# Over_Discharge_Protection_SCHEMATIC.net
KiCad netlist of a schematic drawn in Altium Designer
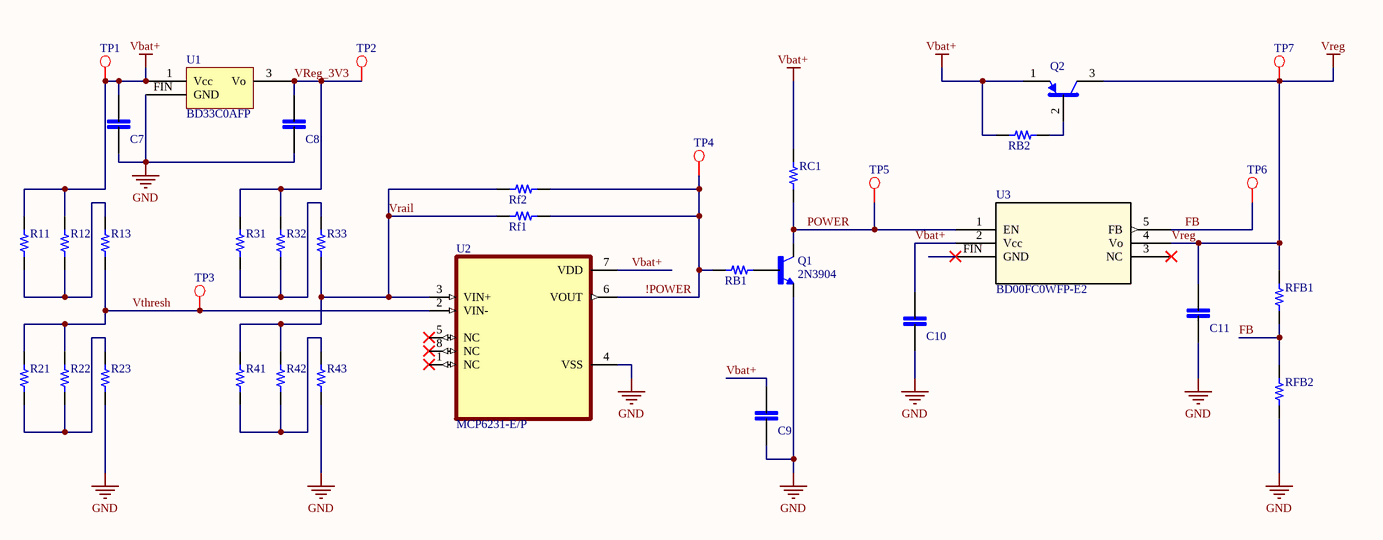
[diagram p0: Over Discharge Protection_SCHEMATIC.SchDoc]

(export (version "E")
  (design (tool "Eeschema 10.0.6"))
  (components
    (comp (ref "C7")
      (value "0805")
      (footprint "Capacitor 0805")
      (libsource (lib "GamePi SCH LIB") (part "Capacitor 0805"))
    )
    (comp (ref "C8")
      (value "0805")
      (footprint "Capacitor 0805")
      (libsource (lib "GamePi SCH LIB") (part "Capacitor 0805"))
    )
    (comp (ref "C9")
      (value "0805")
      (footprint "Capacitor 0805")
      (libsource (lib "GamePi SCH LIB") (part "Capacitor 0805"))
    )
    (comp (ref "C10")
      (value "0805")
      (footprint "Capacitor 0805")
      (libsource (lib "GamePi SCH LIB") (part "Capacitor 0805"))
    )
    (comp (ref "C11")
      (value "0805")
      (footprint "Capacitor 0805")
      (libsource (lib "GamePi SCH LIB") (part "Capacitor 0805"))
    )
    (comp (ref "Q1") (value "2N3904") (footprint "2N3904") (libsource (lib "GamePi SCH LIB") (part "2N3904")))
    (comp (ref "Q2") (value "2N3906") (footprint "2N3904") (libsource (lib "GamePi SCH LIB") (part "2N3906")))
    (comp (ref "R11")
      (value "Resistor Axial")
      (footprint "Resistor Axial")
      (libsource (lib "GamePi SCH LIB") (part "Resistor Axial"))
    )
    (comp (ref "R12")
      (value "Resistor Axial")
      (footprint "Resistor Axial")
      (libsource (lib "GamePi SCH LIB") (part "Resistor Axial"))
    )
    (comp (ref "R13")
      (value "Resistor Axial")
      (footprint "Resistor Axial")
      (libsource (lib "GamePi SCH LIB") (part "Resistor Axial"))
    )
    (comp (ref "R21")
      (value "Resistor Axial")
      (footprint "Resistor Axial")
      (libsource (lib "GamePi SCH LIB") (part "Resistor Axial"))
    )
    (comp (ref "R22")
      (value "Resistor Axial")
      (footprint "Resistor Axial")
      (libsource (lib "GamePi SCH LIB") (part "Resistor Axial"))
    )
    (comp (ref "R23")
      (value "Resistor Axial")
      (footprint "Resistor Axial")
      (libsource (lib "GamePi SCH LIB") (part "Resistor Axial"))
    )
    (comp (ref "R31")
      (value "Resistor Axial")
      (footprint "Resistor Axial")
      (libsource (lib "GamePi SCH LIB") (part "Resistor Axial"))
    )
    (comp (ref "R32")
      (value "Resistor Axial")
      (footprint "Resistor Axial")
      (libsource (lib "GamePi SCH LIB") (part "Resistor Axial"))
    )
    (comp (ref "R33")
      (value "Resistor Axial")
      (footprint "Resistor Axial")
      (libsource (lib "GamePi SCH LIB") (part "Resistor Axial"))
    )
    (comp (ref "R41")
      (value "Resistor Axial")
      (footprint "Resistor Axial")
      (libsource (lib "GamePi SCH LIB") (part "Resistor Axial"))
    )
    (comp (ref "R42")
      (value "Resistor Axial")
      (footprint "Resistor Axial")
      (libsource (lib "GamePi SCH LIB") (part "Resistor Axial"))
    )
    (comp (ref "R43")
      (value "Resistor Axial")
      (footprint "Resistor Axial")
      (libsource (lib "GamePi SCH LIB") (part "Resistor Axial"))
    )
    (comp (ref "RB1")
      (value "Resistor Axial")
      (footprint "Resistor Axial")
      (libsource (lib "GamePi SCH LIB") (part "Resistor Axial"))
    )
    (comp (ref "RB2")
      (value "Resistor Axial")
      (footprint "Resistor Axial")
      (libsource (lib "GamePi SCH LIB") (part "Resistor Axial"))
    )
    (comp (ref "RC1")
      (value "Resistor Axial")
      (footprint "Resistor Axial")
      (libsource (lib "GamePi SCH LIB") (part "Resistor Axial"))
    )
    (comp (ref "Rf1")
      (value "Resistor Axial")
      (footprint "Resistor Axial")
      (libsource (lib "GamePi SCH LIB") (part "Resistor Axial"))
    )
    (comp (ref "Rf2")
      (value "Resistor Axial")
      (footprint "Resistor Axial")
      (libsource (lib "GamePi SCH LIB") (part "Resistor Axial"))
    )
    (comp (ref "RFB1")
      (value "Resistor Axial")
      (footprint "Resistor Axial")
      (libsource (lib "GamePi SCH LIB") (part "Resistor Axial"))
    )
    (comp (ref "RFB2")
      (value "Resistor Axial")
      (footprint "Resistor Axial")
      (libsource (lib "GamePi SCH LIB") (part "Resistor Axial"))
    )
    (comp (ref "TP1")
      (value "Test Point")
      (footprint "Test Point")
      (libsource (lib "GamePi SCH LIB") (part "Test Point"))
    )
    (comp (ref "TP2")
      (value "Test Point")
      (footprint "Test Point")
      (libsource (lib "GamePi SCH LIB") (part "Test Point"))
    )
    (comp (ref "TP3")
      (value "Test Point")
      (footprint "Test Point")
      (libsource (lib "GamePi SCH LIB") (part "Test Point"))
    )
    (comp (ref "TP4")
      (value "Test Point")
      (footprint "Test Point")
      (libsource (lib "GamePi SCH LIB") (part "Test Point"))
    )
    (comp (ref "TP5")
      (value "Test Point")
      (footprint "Test Point")
      (libsource (lib "GamePi SCH LIB") (part "Test Point"))
    )
    (comp (ref "TP6")
      (value "Test Point")
      (footprint "Test Point")
      (libsource (lib "GamePi SCH LIB") (part "Test Point"))
    )
    (comp (ref "TP7")
      (value "Test Point")
      (footprint "Test Point")
      (libsource (lib "GamePi SCH LIB") (part "Test Point"))
    )
    (comp (ref "U1")
      (value "BD33C0AFP")
      (footprint "BD33C0AFP")
      (libsource (lib "GamePi SCH LIB") (part "BD33C0AFP"))
    )
    (comp (ref "U2")
      (value "MCP6231-E/P")
      (footprint "MCP6231-E/P")
      (libsource (lib "GamePi SCH LIB") (part "MCP6231-E/P"))
    )
    (comp (ref "U3")
      (value "BD00FC0WFP-E2")
      (footprint "BD00FC0WFP-E2")
      (libsource (lib "GamePi SCH LIB") (part "BD00FC0WFP-E2"))
    )
  )
  (nets
    (net (code "1") (name "/!POWER") (class "Default")
      (node (ref "RB1") (pin "2") (pinfunction "2_2") (pintype "passive"))
      (node (ref "Rf1") (pin "1") (pinfunction "1_1") (pintype "passive"))
      (node (ref "Rf2") (pin "1") (pinfunction "1_1") (pintype "passive"))
      (node (ref "TP4") (pin "TP?") (pinfunction "Test_Point_TP?") (pintype "passive"))
      (node (ref "U2") (pin "6") (pinfunction "VOUT_6") (pintype "output"))
    )
    (net (code "2") (name "/FB") (class "Default")
      (node (ref "RFB1") (pin "1") (pinfunction "1_1") (pintype "passive"))
      (node (ref "RFB2") (pin "2") (pinfunction "2_2") (pintype "passive"))
      (node (ref "TP6") (pin "TP?") (pinfunction "Test_Point_TP?") (pintype "passive"))
      (node (ref "U3") (pin "5") (pinfunction "FB_5") (pintype "output"))
    )
    (net (code "3") (name "/POWER") (class "Default")
      (node (ref "Q1") (pin "3") (pinfunction "C_3") (pintype "passive"))
      (node (ref "RC1") (pin "1") (pinfunction "1_1") (pintype "passive"))
      (node (ref "TP5") (pin "TP?") (pinfunction "Test_Point_TP?") (pintype "passive"))
      (node (ref "U3") (pin "1") (pinfunction "EN_1") (pintype "power_in"))
    )
    (net (code "4") (name "/VReg_3V3") (class "Default")
      (node (ref "C8") (pin "2") (pinfunction "2_2") (pintype "passive"))
      (node (ref "R31") (pin "2") (pinfunction "2_2") (pintype "passive"))
      (node (ref "R32") (pin "2") (pinfunction "2_2") (pintype "passive"))
      (node (ref "TP2") (pin "TP?") (pinfunction "Test_Point_TP?") (pintype "passive"))
      (node (ref "U1") (pin "3") (pinfunction "Vo_3") (pintype "passive"))
    )
    (net (code "5") (name "/Vrail") (class "Default")
      (node (ref "R33") (pin "1") (pinfunction "1_1") (pintype "passive"))
      (node (ref "R41") (pin "2") (pinfunction "2_2") (pintype "passive"))
      (node (ref "R42") (pin "2") (pinfunction "2_2") (pintype "passive"))
      (node (ref "Rf1") (pin "2") (pinfunction "2_2") (pintype "passive"))
      (node (ref "Rf2") (pin "2") (pinfunction "2_2") (pintype "passive"))
      (node (ref "U2") (pin "3") (pinfunction "VIN+_3") (pintype "input"))
    )
    (net (code "6") (name "/Vthresh") (class "Default")
      (node (ref "R13") (pin "1") (pinfunction "1_1") (pintype "passive"))
      (node (ref "R21") (pin "2") (pinfunction "2_2") (pintype "passive"))
      (node (ref "R22") (pin "2") (pinfunction "2_2") (pintype "passive"))
      (node (ref "TP3") (pin "TP?") (pinfunction "Test_Point_TP?") (pintype "passive"))
      (node (ref "U2") (pin "2") (pinfunction "VIN-_2") (pintype "input"))
    )
    (net (code "7") (name "GND") (class "Default")
      (node (ref "C10") (pin "1") (pinfunction "1_1") (pintype "passive"))
      (node (ref "C11") (pin "1") (pinfunction "1_1") (pintype "passive"))
      (node (ref "C7") (pin "1") (pinfunction "1_1") (pintype "passive"))
      (node (ref "C8") (pin "1") (pinfunction "1_1") (pintype "passive"))
      (node (ref "C9") (pin "1") (pinfunction "1_1") (pintype "passive"))
      (node (ref "Q1") (pin "1") (pinfunction "E_1") (pintype "passive"))
      (node (ref "R23") (pin "1") (pinfunction "1_1") (pintype "passive"))
      (node (ref "R43") (pin "1") (pinfunction "1_1") (pintype "passive"))
      (node (ref "RFB2") (pin "1") (pinfunction "1_1") (pintype "passive"))
      (node (ref "U1") (pin "FIN") (pinfunction "GND_FIN") (pintype "passive"))
      (node (ref "U2") (pin "4") (pinfunction "VSS_4") (pintype "power_in"))
    )
    (net (code "8") (name "Net-(Q1-B)") (class "Default")
      (node (ref "Q1") (pin "2") (pinfunction "B_2") (pintype "passive"))
      (node (ref "RB1") (pin "1") (pinfunction "1_1") (pintype "passive"))
    )
    (net (code "9") (name "Net-(Q2-B)") (class "Default")
      (node (ref "Q2") (pin "2") (pinfunction "B_2") (pintype "passive"))
      (node (ref "RB2") (pin "1") (pinfunction "1_1") (pintype "passive"))
    )
    (net (code "10") (name "Net-(R11-Pad1)") (class "Default")
      (node (ref "R11") (pin "1") (pinfunction "1_1") (pintype "passive"))
      (node (ref "R12") (pin "1") (pinfunction "1_1") (pintype "passive"))
      (node (ref "R13") (pin "2") (pinfunction "2_2") (pintype "passive"))
    )
    (net (code "11") (name "Net-(R21-Pad1)") (class "Default")
      (node (ref "R21") (pin "1") (pinfunction "1_1") (pintype "passive"))
      (node (ref "R22") (pin "1") (pinfunction "1_1") (pintype "passive"))
      (node (ref "R23") (pin "2") (pinfunction "2_2") (pintype "passive"))
    )
    (net (code "12") (name "Net-(R31-Pad1)") (class "Default")
      (node (ref "R31") (pin "1") (pinfunction "1_1") (pintype "passive"))
      (node (ref "R32") (pin "1") (pinfunction "1_1") (pintype "passive"))
      (node (ref "R33") (pin "2") (pinfunction "2_2") (pintype "passive"))
    )
    (net (code "13") (name "Net-(R41-Pad1)") (class "Default")
      (node (ref "R41") (pin "1") (pinfunction "1_1") (pintype "passive"))
      (node (ref "R42") (pin "1") (pinfunction "1_1") (pintype "passive"))
      (node (ref "R43") (pin "2") (pinfunction "2_2") (pintype "passive"))
    )
    (net (code "14") (name "Vbat+") (class "Default")
      (node (ref "C10") (pin "2") (pinfunction "2_2") (pintype "passive"))
      (node (ref "C7") (pin "2") (pinfunction "2_2") (pintype "passive"))
      (node (ref "C9") (pin "2") (pinfunction "2_2") (pintype "passive"))
      (node (ref "Q2") (pin "1") (pinfunction "E_1") (pintype "passive"))
      (node (ref "R11") (pin "2") (pinfunction "2_2") (pintype "passive"))
      (node (ref "R12") (pin "2") (pinfunction "2_2") (pintype "passive"))
      (node (ref "RB2") (pin "2") (pinfunction "2_2") (pintype "passive"))
      (node (ref "RC1") (pin "2") (pinfunction "2_2") (pintype "passive"))
      (node (ref "TP1") (pin "TP?") (pinfunction "Test_Point_TP?") (pintype "passive"))
      (node (ref "U1") (pin "1") (pinfunction "Vcc_1") (pintype "passive"))
      (node (ref "U2") (pin "7") (pinfunction "VDD_7") (pintype "power_in"))
      (node (ref "U3") (pin "2") (pinfunction "Vcc_2") (pintype "passive"))
    )
    (net (code "15") (name "Vreg") (class "Default")
      (node (ref "C11") (pin "2") (pinfunction "2_2") (pintype "passive"))
      (node (ref "Q2") (pin "3") (pinfunction "C_3") (pintype "passive"))
      (node (ref "RFB1") (pin "2") (pinfunction "2_2") (pintype "passive"))
      (node (ref "TP7") (pin "TP?") (pinfunction "Test_Point_TP?") (pintype "passive"))
      (node (ref "U3") (pin "4") (pinfunction "Vo_4") (pintype "power_in"))
    )
    (net (code "16") (name "unconnected-(U2-NC-Pad1)") (class "Default")
      (node (ref "U2") (pin "1") (pinfunction "NC_1") (pintype "bidirectional+no_connect"))
    )
    (net (code "17") (name "unconnected-(U2-NC-Pad5)") (class "Default")
      (node (ref "U2") (pin "5") (pinfunction "NC_5") (pintype "bidirectional+no_connect"))
    )
    (net (code "18") (name "unconnected-(U2-NC-Pad8)") (class "Default")
      (node (ref "U2") (pin "8") (pinfunction "NC_8") (pintype "bidirectional+no_connect"))
    )
    (net (code "19") (name "unconnected-(U3-GND-PadFIN)") (class "Default")
      (node (ref "U3") (pin "FIN") (pinfunction "GND_FIN") (pintype "passive+no_connect"))
    )
    (net (code "20") (name "unconnected-(U3-NC-Pad3)") (class "Default")
      (node (ref "U3") (pin "3") (pinfunction "NC_3") (pintype "power_in+no_connect"))
    )
  )
)
